# pcb-breakout-bgm111.net
KiCad netlist of a schematic drawn in EAGLE
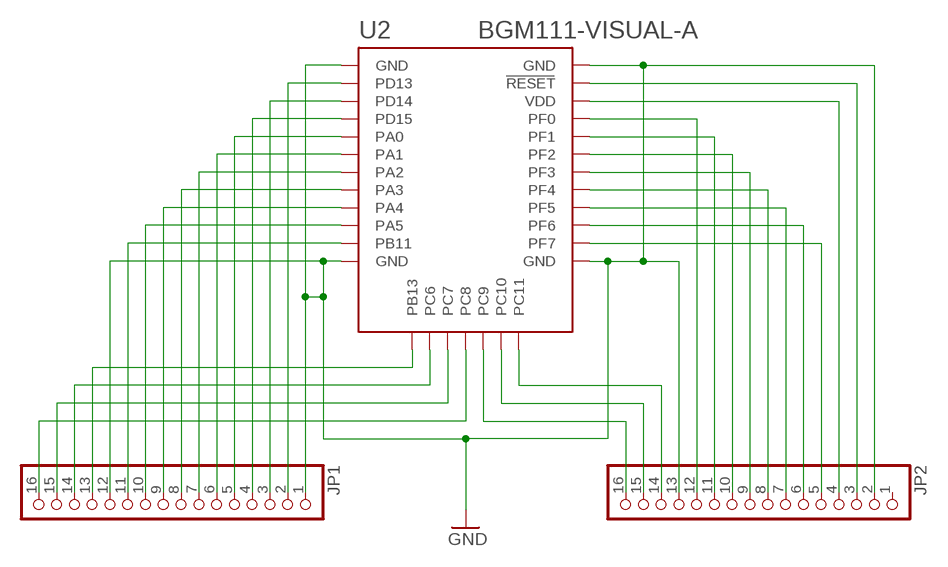
[diagram p0: schematic, sheet 1]

(export (version "E")
  (design (tool "Eeschema 10.0.6"))
  (components
    (comp (ref "JP1")
      (value "PINHD-1X16")
      (footprint "eagle-import:1X16")
      (libsource (lib "eagle-import") (part "PINHD-1X16"))
    )
    (comp (ref "JP2")
      (value "PINHD-1X16")
      (footprint "eagle-import:1X16")
      (libsource (lib "eagle-import") (part "PINHD-1X16"))
    )
    (comp (ref "U2")
      (value "BGM111-VISUAL-A")
      (footprint "eagle-import:BGM111-A")
      (libsource (lib "eagle-import") (part "BGM111-VISUAL-A"))
    )
  )
  (nets
    (net (code "1") (name "GND") (class "Default")
      (node (ref "JP1") (pin "1") (pinfunction "1_1") (pintype "passive"))
      (node (ref "JP1") (pin "12") (pinfunction "12_12") (pintype "passive"))
      (node (ref "JP2") (pin "13") (pinfunction "13_13") (pintype "passive"))
      (node (ref "JP2") (pin "2") (pinfunction "2_2") (pintype "passive"))
      (node (ref "U2") (pin "GND") (pinfunction "GND_GND") (pintype "power_in"))
      (node (ref "U2") (pin "GND@2") (pinfunction "GND_GND@2") (pintype "power_in"))
      (node (ref "U2") (pin "GND@3") (pinfunction "GND_GND@3") (pintype "power_in"))
      (node (ref "U2") (pin "GND@4") (pinfunction "GND_GND@4") (pintype "power_in"))
    )
    (net (code "2") (name "Net-(JP1-Pad2)") (class "Default")
      (node (ref "JP1") (pin "2") (pinfunction "2_2") (pintype "passive"))
      (node (ref "U2") (pin "PD13") (pinfunction "PD13_PD13") (pintype "bidirectional"))
    )
    (net (code "3") (name "Net-(JP1-Pad3)") (class "Default")
      (node (ref "JP1") (pin "3") (pinfunction "3_3") (pintype "passive"))
      (node (ref "U2") (pin "PD14") (pinfunction "PD14_PD14") (pintype "bidirectional"))
    )
    (net (code "4") (name "Net-(JP1-Pad4)") (class "Default")
      (node (ref "JP1") (pin "4") (pinfunction "4_4") (pintype "passive"))
      (node (ref "U2") (pin "PD15") (pinfunction "PD15_PD15") (pintype "bidirectional"))
    )
    (net (code "5") (name "Net-(JP1-Pad5)") (class "Default")
      (node (ref "JP1") (pin "5") (pinfunction "5_5") (pintype "passive"))
      (node (ref "U2") (pin "PA0") (pinfunction "PA0_PA0") (pintype "bidirectional"))
    )
    (net (code "6") (name "Net-(JP1-Pad6)") (class "Default")
      (node (ref "JP1") (pin "6") (pinfunction "6_6") (pintype "passive"))
      (node (ref "U2") (pin "PA1") (pinfunction "PA1_PA1") (pintype "bidirectional"))
    )
    (net (code "7") (name "Net-(JP1-Pad7)") (class "Default")
      (node (ref "JP1") (pin "7") (pinfunction "7_7") (pintype "passive"))
      (node (ref "U2") (pin "PA2") (pinfunction "PA2_PA2") (pintype "bidirectional"))
    )
    (net (code "8") (name "Net-(JP1-Pad8)") (class "Default")
      (node (ref "JP1") (pin "8") (pinfunction "8_8") (pintype "passive"))
      (node (ref "U2") (pin "PA3") (pinfunction "PA3_PA3") (pintype "bidirectional"))
    )
    (net (code "9") (name "Net-(JP1-Pad9)") (class "Default")
      (node (ref "JP1") (pin "9") (pinfunction "9_9") (pintype "passive"))
      (node (ref "U2") (pin "PA4") (pinfunction "PA4_PA4") (pintype "bidirectional"))
    )
    (net (code "10") (name "Net-(JP1-Pad10)") (class "Default")
      (node (ref "JP1") (pin "10") (pinfunction "10_10") (pintype "passive"))
      (node (ref "U2") (pin "PA5") (pinfunction "PA5_PA5") (pintype "bidirectional"))
    )
    (net (code "11") (name "Net-(JP1-Pad11)") (class "Default")
      (node (ref "JP1") (pin "11") (pinfunction "11_11") (pintype "passive"))
      (node (ref "U2") (pin "PB11") (pinfunction "PB11_PB11") (pintype "bidirectional"))
    )
    (net (code "12") (name "Net-(JP1-Pad13)") (class "Default")
      (node (ref "JP1") (pin "13") (pinfunction "13_13") (pintype "passive"))
      (node (ref "U2") (pin "PB13") (pinfunction "PB13_PB13") (pintype "bidirectional"))
    )
    (net (code "13") (name "Net-(JP1-Pad14)") (class "Default")
      (node (ref "JP1") (pin "14") (pinfunction "14_14") (pintype "passive"))
      (node (ref "U2") (pin "PC6") (pinfunction "PC6_PC6") (pintype "bidirectional"))
    )
    (net (code "14") (name "Net-(JP1-Pad15)") (class "Default")
      (node (ref "JP1") (pin "15") (pinfunction "15_15") (pintype "passive"))
      (node (ref "U2") (pin "PC7") (pinfunction "PC7_PC7") (pintype "bidirectional"))
    )
    (net (code "15") (name "Net-(JP1-Pad16)") (class "Default")
      (node (ref "JP1") (pin "16") (pinfunction "16_16") (pintype "passive"))
      (node (ref "U2") (pin "PC8") (pinfunction "PC8_PC8") (pintype "bidirectional"))
    )
    (net (code "16") (name "Net-(JP2-Pad3)") (class "Default")
      (node (ref "JP2") (pin "3") (pinfunction "3_3") (pintype "passive"))
      (node (ref "U2") (pin "RESET") (pinfunction "RESET_RESET") (pintype "input"))
    )
    (net (code "17") (name "Net-(JP2-Pad4)") (class "Default")
      (node (ref "JP2") (pin "4") (pinfunction "4_4") (pintype "passive"))
      (node (ref "U2") (pin "VDD") (pinfunction "VDD_VDD") (pintype "power_in"))
    )
    (net (code "18") (name "Net-(JP2-Pad5)") (class "Default")
      (node (ref "JP2") (pin "5") (pinfunction "5_5") (pintype "passive"))
      (node (ref "U2") (pin "PF7") (pinfunction "PF7_PF7") (pintype "bidirectional"))
    )
    (net (code "19") (name "Net-(JP2-Pad6)") (class "Default")
      (node (ref "JP2") (pin "6") (pinfunction "6_6") (pintype "passive"))
      (node (ref "U2") (pin "PF6") (pinfunction "PF6_PF6") (pintype "bidirectional"))
    )
    (net (code "20") (name "Net-(JP2-Pad7)") (class "Default")
      (node (ref "JP2") (pin "7") (pinfunction "7_7") (pintype "passive"))
      (node (ref "U2") (pin "PF5") (pinfunction "PF5_PF5") (pintype "bidirectional"))
    )
    (net (code "21") (name "Net-(JP2-Pad8)") (class "Default")
      (node (ref "JP2") (pin "8") (pinfunction "8_8") (pintype "passive"))
      (node (ref "U2") (pin "PF4") (pinfunction "PF4_PF4") (pintype "bidirectional"))
    )
    (net (code "22") (name "Net-(JP2-Pad9)") (class "Default")
      (node (ref "JP2") (pin "9") (pinfunction "9_9") (pintype "passive"))
      (node (ref "U2") (pin "PF3") (pinfunction "PF3_PF3") (pintype "bidirectional"))
    )
    (net (code "23") (name "Net-(JP2-Pad10)") (class "Default")
      (node (ref "JP2") (pin "10") (pinfunction "10_10") (pintype "passive"))
      (node (ref "U2") (pin "PF2") (pinfunction "PF2_PF2") (pintype "bidirectional"))
    )
    (net (code "24") (name "Net-(JP2-Pad11)") (class "Default")
      (node (ref "JP2") (pin "11") (pinfunction "11_11") (pintype "passive"))
      (node (ref "U2") (pin "PF1") (pinfunction "PF1_PF1") (pintype "bidirectional"))
    )
    (net (code "25") (name "Net-(JP2-Pad12)") (class "Default")
      (node (ref "JP2") (pin "12") (pinfunction "12_12") (pintype "passive"))
      (node (ref "U2") (pin "PF0") (pinfunction "PF0_PF0") (pintype "bidirectional"))
    )
    (net (code "26") (name "Net-(JP2-Pad14)") (class "Default")
      (node (ref "JP2") (pin "14") (pinfunction "14_14") (pintype "passive"))
      (node (ref "U2") (pin "PC11") (pinfunction "PC11_PC11") (pintype "bidirectional"))
    )
    (net (code "27") (name "Net-(JP2-Pad15)") (class "Default")
      (node (ref "JP2") (pin "15") (pinfunction "15_15") (pintype "passive"))
      (node (ref "U2") (pin "PC10") (pinfunction "PC10_PC10") (pintype "bidirectional"))
    )
    (net (code "28") (name "Net-(JP2-Pad16)") (class "Default")
      (node (ref "JP2") (pin "16") (pinfunction "16_16") (pintype "passive"))
      (node (ref "U2") (pin "PC9") (pinfunction "PC9_PC9") (pintype "bidirectional"))
    )
    (net (code "29") (name "unconnected-(JP2-Pad1)") (class "Default")
      (node (ref "JP2") (pin "1") (pinfunction "1_1") (pintype "passive"))
    )
  )
)
